# power.net
KiCad netlist of a schematic drawn in Altium Designer
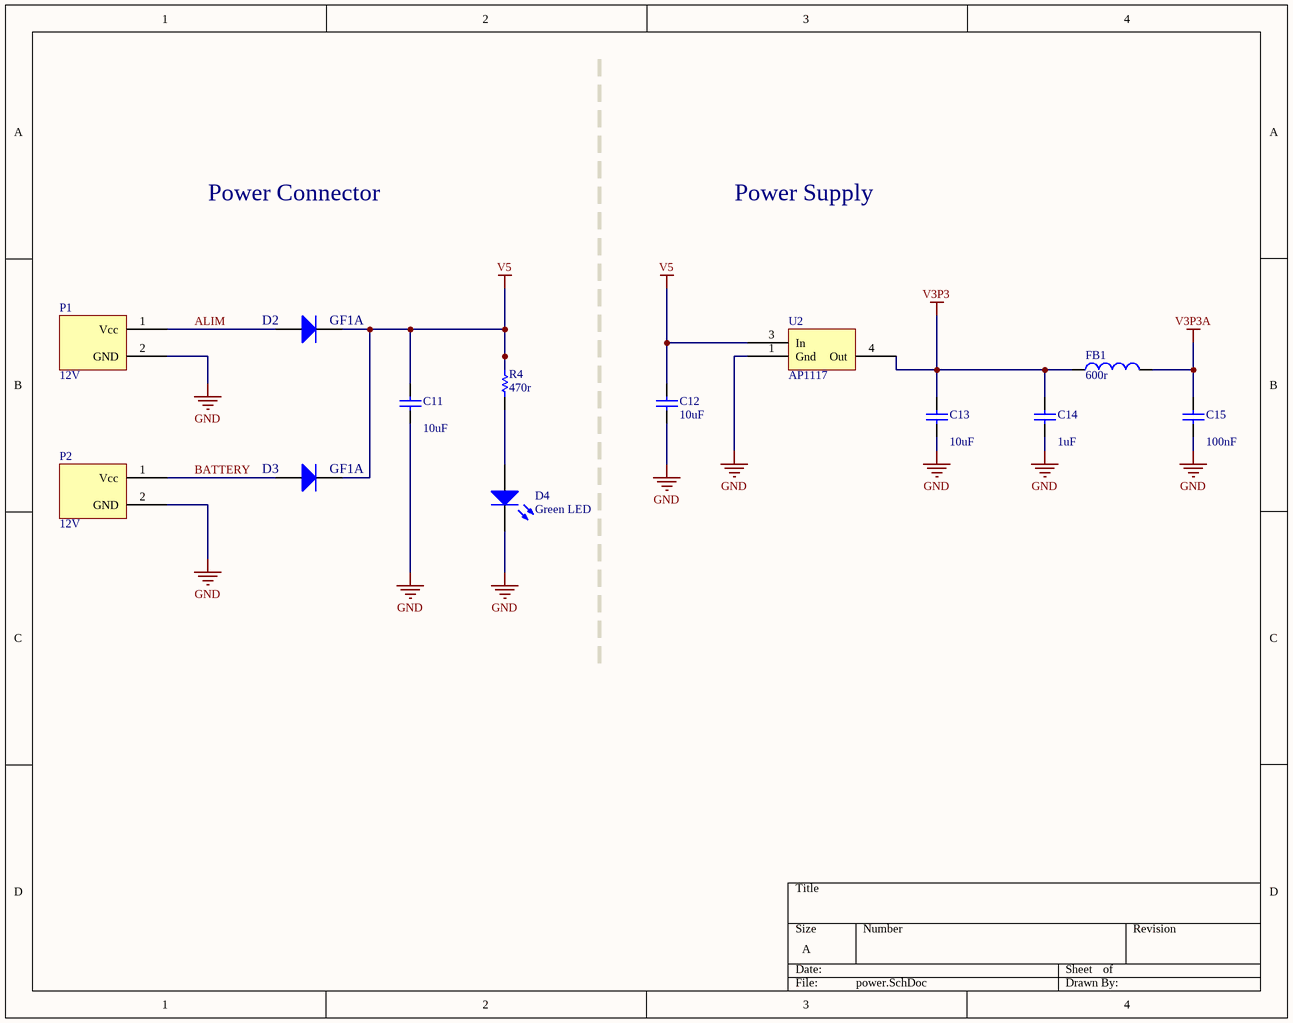
[diagram p0: power.SchDoc]

(export (version "E")
  (design (tool "Eeschema 10.0.6"))
  (components
    (comp (ref "C11")
      (value "10uF")
      (footprint "PcbLib_2:CAPC2012N")
      (description "Capacitor")
      (fields (field (name "PUBLISHER") "Altium Limited"))
      (libsource (lib "Miscellaneous Devices") (part "Cap"))
    )
    (comp (ref "C12")
      (value "10uF")
      (footprint "PcbLib_2:CAPC2012N")
      (description "Capacitor")
      (fields (field (name "PUBLISHER") "Altium Limited"))
      (libsource (lib "Miscellaneous Devices") (part "Cap"))
    )
    (comp (ref "C13")
      (value "10uF")
      (footprint "PcbLib_2:CAPC2012N")
      (description "Capacitor")
      (fields (field (name "Comment") "Cap") (field (name "PUBLISHER") "Altium Limited"))
      (libsource (lib "Miscellaneous Devices") (part "Cap"))
    )
    (comp (ref "C14")
      (value "1uF")
      (footprint "PcbLib_2:CAPC1608N")
      (description "Capacitor")
      (fields (field (name "Comment") "Cap") (field (name "PUBLISHER") "Altium Limited"))
      (libsource (lib "Miscellaneous Devices") (part "Cap"))
    )
    (comp (ref "C15")
      (value "100nF")
      (footprint "PcbLib_2:CAPC1608N")
      (description "Capacitor")
      (fields (field (name "Comment") "Cap") (field (name "PUBLISHER") "Altium Limited"))
      (libsource (lib "Miscellaneous Devices") (part "Cap"))
    )
    (comp (ref "D2")
      (value "Diode")
      (footprint "PcbLib_2:SMA/DO-214AC_21")
      (description "Default Diode")
      (fields (field (name "PUBLISHER") "Altium Limited"))
      (libsource (lib "Miscellaneous Devices") (part "Diode"))
    )
    (comp (ref "D3")
      (value "Diode")
      (footprint "PcbLib_2:SMA/DO-214AC_21")
      (description "Default Diode")
      (fields (field (name "PUBLISHER") "Altium Limited"))
      (libsource (lib "Miscellaneous Devices") (part "Diode"))
    )
    (comp (ref "D4")
      (value "Green LED")
      (footprint "PcbLib_2:LED 0805")
      (description "Typical INFRARED GaAs LED")
      (fields (field (name "PUBLISHER") "Altium Limited"))
      (libsource (lib "Miscellaneous Devices") (part "LED0"))
    )
    (comp (ref "FB1")
      (value "600r")
      (footprint "PcbLib_1:INDC1608AN")
      (description "Inductor")
      (fields (field (name "PUBLISHER") "Altium Limited"))
      (libsource (lib "Miscellaneous Devices") (part "Inductor"))
    )
    (comp (ref "P1")
      (value "12V")
      (footprint "PcbLib_2:PHOENIX_1985195")
      (libsource (lib "LibSch") (part "12V"))
    )
    (comp (ref "P2")
      (value "12V")
      (footprint "PcbLib_2:PHOENIX_1985195")
      (libsource (lib "LibSch") (part "12V"))
    )
    (comp (ref "R4")
      (value "470r")
      (footprint "PcbLib_2:RESC1608N")
      (description "Resistor")
      (fields (field (name "PUBLISHER") "Altium Limited"))
      (libsource (lib "Miscellaneous Devices") (part "Res1"))
    )
    (comp (ref "U2")
      (value "AP1117")
      (footprint "PcbLib_1:TD03B_N")
      (libsource (lib "LibSch") (part "AP1117"))
    )
  )
  (nets
    (net (code "1") (name "/ALIM") (class "Default")
      (node (ref "D2") (pin "1") (pinfunction "A_1") (pintype "passive"))
      (node (ref "P1") (pin "1") (pinfunction "Vcc_1") (pintype "passive"))
    )
    (net (code "2") (name "/BATTERY") (class "Default")
      (node (ref "D3") (pin "1") (pinfunction "A_1") (pintype "passive"))
      (node (ref "P2") (pin "1") (pinfunction "Vcc_1") (pintype "passive"))
    )
    (net (code "3") (name "GND") (class "Default")
      (node (ref "C11") (pin "1") (pinfunction "1_1") (pintype "passive"))
      (node (ref "C12") (pin "1") (pinfunction "1_1") (pintype "passive"))
      (node (ref "C13") (pin "1") (pinfunction "1_1") (pintype "passive"))
      (node (ref "C14") (pin "1") (pinfunction "1_1") (pintype "passive"))
      (node (ref "C15") (pin "1") (pinfunction "1_1") (pintype "passive"))
      (node (ref "D4") (pin "2") (pinfunction "K_2") (pintype "passive"))
      (node (ref "P1") (pin "2") (pinfunction "GND_2") (pintype "passive"))
      (node (ref "P2") (pin "2") (pinfunction "GND_2") (pintype "passive"))
      (node (ref "U2") (pin "1") (pinfunction "Gnd_1") (pintype "passive"))
    )
    (net (code "4") (name "Net-(D4-A)") (class "Default")
      (node (ref "D4") (pin "1") (pinfunction "A_1") (pintype "passive"))
      (node (ref "R4") (pin "1") (pinfunction "1_1") (pintype "passive"))
    )
    (net (code "5") (name "V3P3") (class "Default")
      (node (ref "C13") (pin "2") (pinfunction "2_2") (pintype "passive"))
      (node (ref "C14") (pin "2") (pinfunction "2_2") (pintype "passive"))
      (node (ref "FB1") (pin "1") (pinfunction "1_1") (pintype "passive"))
      (node (ref "U2") (pin "4") (pinfunction "Out_4") (pintype "passive"))
    )
    (net (code "6") (name "V3P3A") (class "Default")
      (node (ref "C15") (pin "2") (pinfunction "2_2") (pintype "passive"))
      (node (ref "FB1") (pin "2") (pinfunction "2_2") (pintype "passive"))
    )
    (net (code "7") (name "V5") (class "Default")
      (node (ref "C11") (pin "2") (pinfunction "2_2") (pintype "passive"))
      (node (ref "C12") (pin "2") (pinfunction "2_2") (pintype "passive"))
      (node (ref "D2") (pin "2") (pinfunction "K_2") (pintype "passive"))
      (node (ref "D3") (pin "2") (pinfunction "K_2") (pintype "passive"))
      (node (ref "R4") (pin "2") (pinfunction "2_2") (pintype "passive"))
      (node (ref "U2") (pin "3") (pinfunction "In_3") (pintype "passive"))
    )
  )
)
